# esquematico.net
KiCad netlist of a schematic drawn in EAGLE
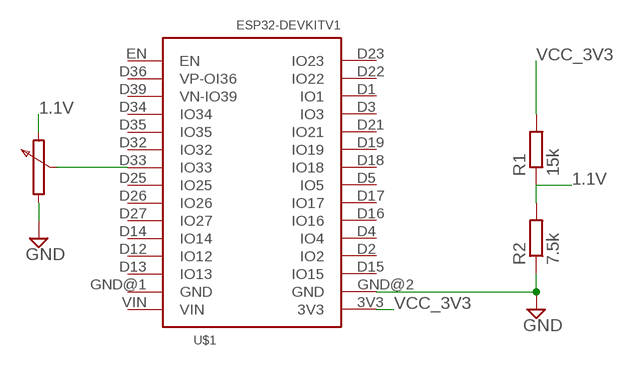
[diagram p0: schematic, sheet 1]

(export (version "E")
  (design (tool "Eeschema 10.0.6"))
  (components
    (comp (ref "R1")
      (value "15k")
      (footprint "eagle-import:0204_5")
      (libsource (lib "eagle-import") (part "R-EU_0204/5"))
    )
    (comp (ref "R2")
      (value "7.5k")
      (footprint "eagle-import:0204_5")
      (libsource (lib "eagle-import") (part "R-EU_0204/5"))
    )
    (comp (ref "U$1")
      (value "ESP32DEVKITV1")
      (footprint "eagle-import:ESP32-DEVKITV1")
      (libsource (lib "eagle-import") (part "ESP32DEVKITV1"))
    )
  )
  (nets
    (net (code "1") (name "/1.1V") (class "Default")
      (node (ref "R1") (pin "1") (pinfunction "1_1") (pintype "passive"))
      (node (ref "R2") (pin "2") (pinfunction "2_2") (pintype "passive"))
    )
    (net (code "2") (name "/VCC_3V3") (class "Default")
      (node (ref "R1") (pin "2") (pinfunction "2_2") (pintype "passive"))
      (node (ref "U$1") (pin "3V3") (pinfunction "3V3_3V3") (pintype "bidirectional"))
    )
    (net (code "3") (name "GND") (class "Default")
      (node (ref "R2") (pin "1") (pinfunction "1_1") (pintype "passive"))
      (node (ref "U$1") (pin "GND@2") (pinfunction "GND_GND@2") (pintype "bidirectional"))
    )
    (net (code "4") (name "unconnected-(U$1-GND-PadGND@1)") (class "Default")
      (node (ref "U$1") (pin "GND@1") (pinfunction "GND_GND@1") (pintype "bidirectional"))
    )
    (net (code "5") (name "unconnected-(U$1-IO1-PadD1)") (class "Default")
      (node (ref "U$1") (pin "D1") (pinfunction "IO1_D1") (pintype "bidirectional"))
    )
    (net (code "6") (name "unconnected-(U$1-IO2-PadD2)") (class "Default")
      (node (ref "U$1") (pin "D2") (pinfunction "IO2_D2") (pintype "bidirectional"))
    )
    (net (code "7") (name "unconnected-(U$1-IO3-PadD3)") (class "Default")
      (node (ref "U$1") (pin "D3") (pinfunction "IO3_D3") (pintype "bidirectional"))
    )
    (net (code "8") (name "unconnected-(U$1-IO4-PadD4)") (class "Default")
      (node (ref "U$1") (pin "D4") (pinfunction "IO4_D4") (pintype "bidirectional"))
    )
    (net (code "9") (name "unconnected-(U$1-IO5-PadD5)") (class "Default")
      (node (ref "U$1") (pin "D5") (pinfunction "IO5_D5") (pintype "bidirectional"))
    )
    (net (code "10") (name "unconnected-(U$1-IO12-PadD12)") (class "Default")
      (node (ref "U$1") (pin "D12") (pinfunction "IO12_D12") (pintype "bidirectional"))
    )
    (net (code "11") (name "unconnected-(U$1-IO13-PadD13)") (class "Default")
      (node (ref "U$1") (pin "D13") (pinfunction "IO13_D13") (pintype "bidirectional"))
    )
    (net (code "12") (name "unconnected-(U$1-IO14-PadD14)") (class "Default")
      (node (ref "U$1") (pin "D14") (pinfunction "IO14_D14") (pintype "bidirectional"))
    )
    (net (code "13") (name "unconnected-(U$1-IO15-PadD15)") (class "Default")
      (node (ref "U$1") (pin "D15") (pinfunction "IO15_D15") (pintype "bidirectional"))
    )
    (net (code "14") (name "unconnected-(U$1-IO16-PadD16)") (class "Default")
      (node (ref "U$1") (pin "D16") (pinfunction "IO16_D16") (pintype "bidirectional"))
    )
    (net (code "15") (name "unconnected-(U$1-IO17-PadD17)") (class "Default")
      (node (ref "U$1") (pin "D17") (pinfunction "IO17_D17") (pintype "bidirectional"))
    )
    (net (code "16") (name "unconnected-(U$1-IO18-PadD18)") (class "Default")
      (node (ref "U$1") (pin "D18") (pinfunction "IO18_D18") (pintype "bidirectional"))
    )
    (net (code "17") (name "unconnected-(U$1-IO19-PadD19)") (class "Default")
      (node (ref "U$1") (pin "D19") (pinfunction "IO19_D19") (pintype "bidirectional"))
    )
    (net (code "18") (name "unconnected-(U$1-IO21-PadD21)") (class "Default")
      (node (ref "U$1") (pin "D21") (pinfunction "IO21_D21") (pintype "bidirectional"))
    )
    (net (code "19") (name "unconnected-(U$1-IO22-PadD22)") (class "Default")
      (node (ref "U$1") (pin "D22") (pinfunction "IO22_D22") (pintype "bidirectional"))
    )
    (net (code "20") (name "unconnected-(U$1-IO23-PadD23)") (class "Default")
      (node (ref "U$1") (pin "D23") (pinfunction "IO23_D23") (pintype "bidirectional"))
    )
    (net (code "21") (name "unconnected-(U$1-IO25-PadD25)") (class "Default")
      (node (ref "U$1") (pin "D25") (pinfunction "IO25_D25") (pintype "bidirectional"))
    )
    (net (code "22") (name "unconnected-(U$1-IO26-PadD26)") (class "Default")
      (node (ref "U$1") (pin "D26") (pinfunction "IO26_D26") (pintype "bidirectional"))
    )
    (net (code "23") (name "unconnected-(U$1-IO27-PadD27)") (class "Default")
      (node (ref "U$1") (pin "D27") (pinfunction "IO27_D27") (pintype "bidirectional"))
    )
    (net (code "24") (name "unconnected-(U$1-IO32-PadD32)") (class "Default")
      (node (ref "U$1") (pin "D32") (pinfunction "IO32_D32") (pintype "bidirectional"))
    )
    (net (code "25") (name "unconnected-(U$1-IO33-PadD33)") (class "Default")
      (node (ref "U$1") (pin "D33") (pinfunction "IO33_D33") (pintype "bidirectional"))
    )
    (net (code "26") (name "unconnected-(U$1-IO34-PadD34)") (class "Default")
      (node (ref "U$1") (pin "D34") (pinfunction "IO34_D34") (pintype "bidirectional"))
    )
    (net (code "27") (name "unconnected-(U$1-IO35-PadD35)") (class "Default")
      (node (ref "U$1") (pin "D35") (pinfunction "IO35_D35") (pintype "bidirectional"))
    )
    (net (code "28") (name "unconnected-(U$1-PadEN)") (class "Default")
      (node (ref "U$1") (pin "EN") (pinfunction "EN_EN") (pintype "bidirectional"))
    )
    (net (code "29") (name "unconnected-(U$1-PadVIN)") (class "Default")
      (node (ref "U$1") (pin "VIN") (pinfunction "VIN_VIN") (pintype "bidirectional"))
    )
    (net (code "30") (name "unconnected-(U$1-VN-IO39-PadD39)") (class "Default")
      (node (ref "U$1") (pin "D39") (pinfunction "VN-IO39_D39") (pintype "bidirectional"))
    )
    (net (code "31") (name "unconnected-(U$1-VP-OI36-PadD36)") (class "Default")
      (node (ref "U$1") (pin "D36") (pinfunction "VP-OI36_D36") (pintype "bidirectional"))
    )
  )
)
